# proyecto_diseno_2025_2.net
KiCad netlist of a schematic drawn in EasyEDA Pro
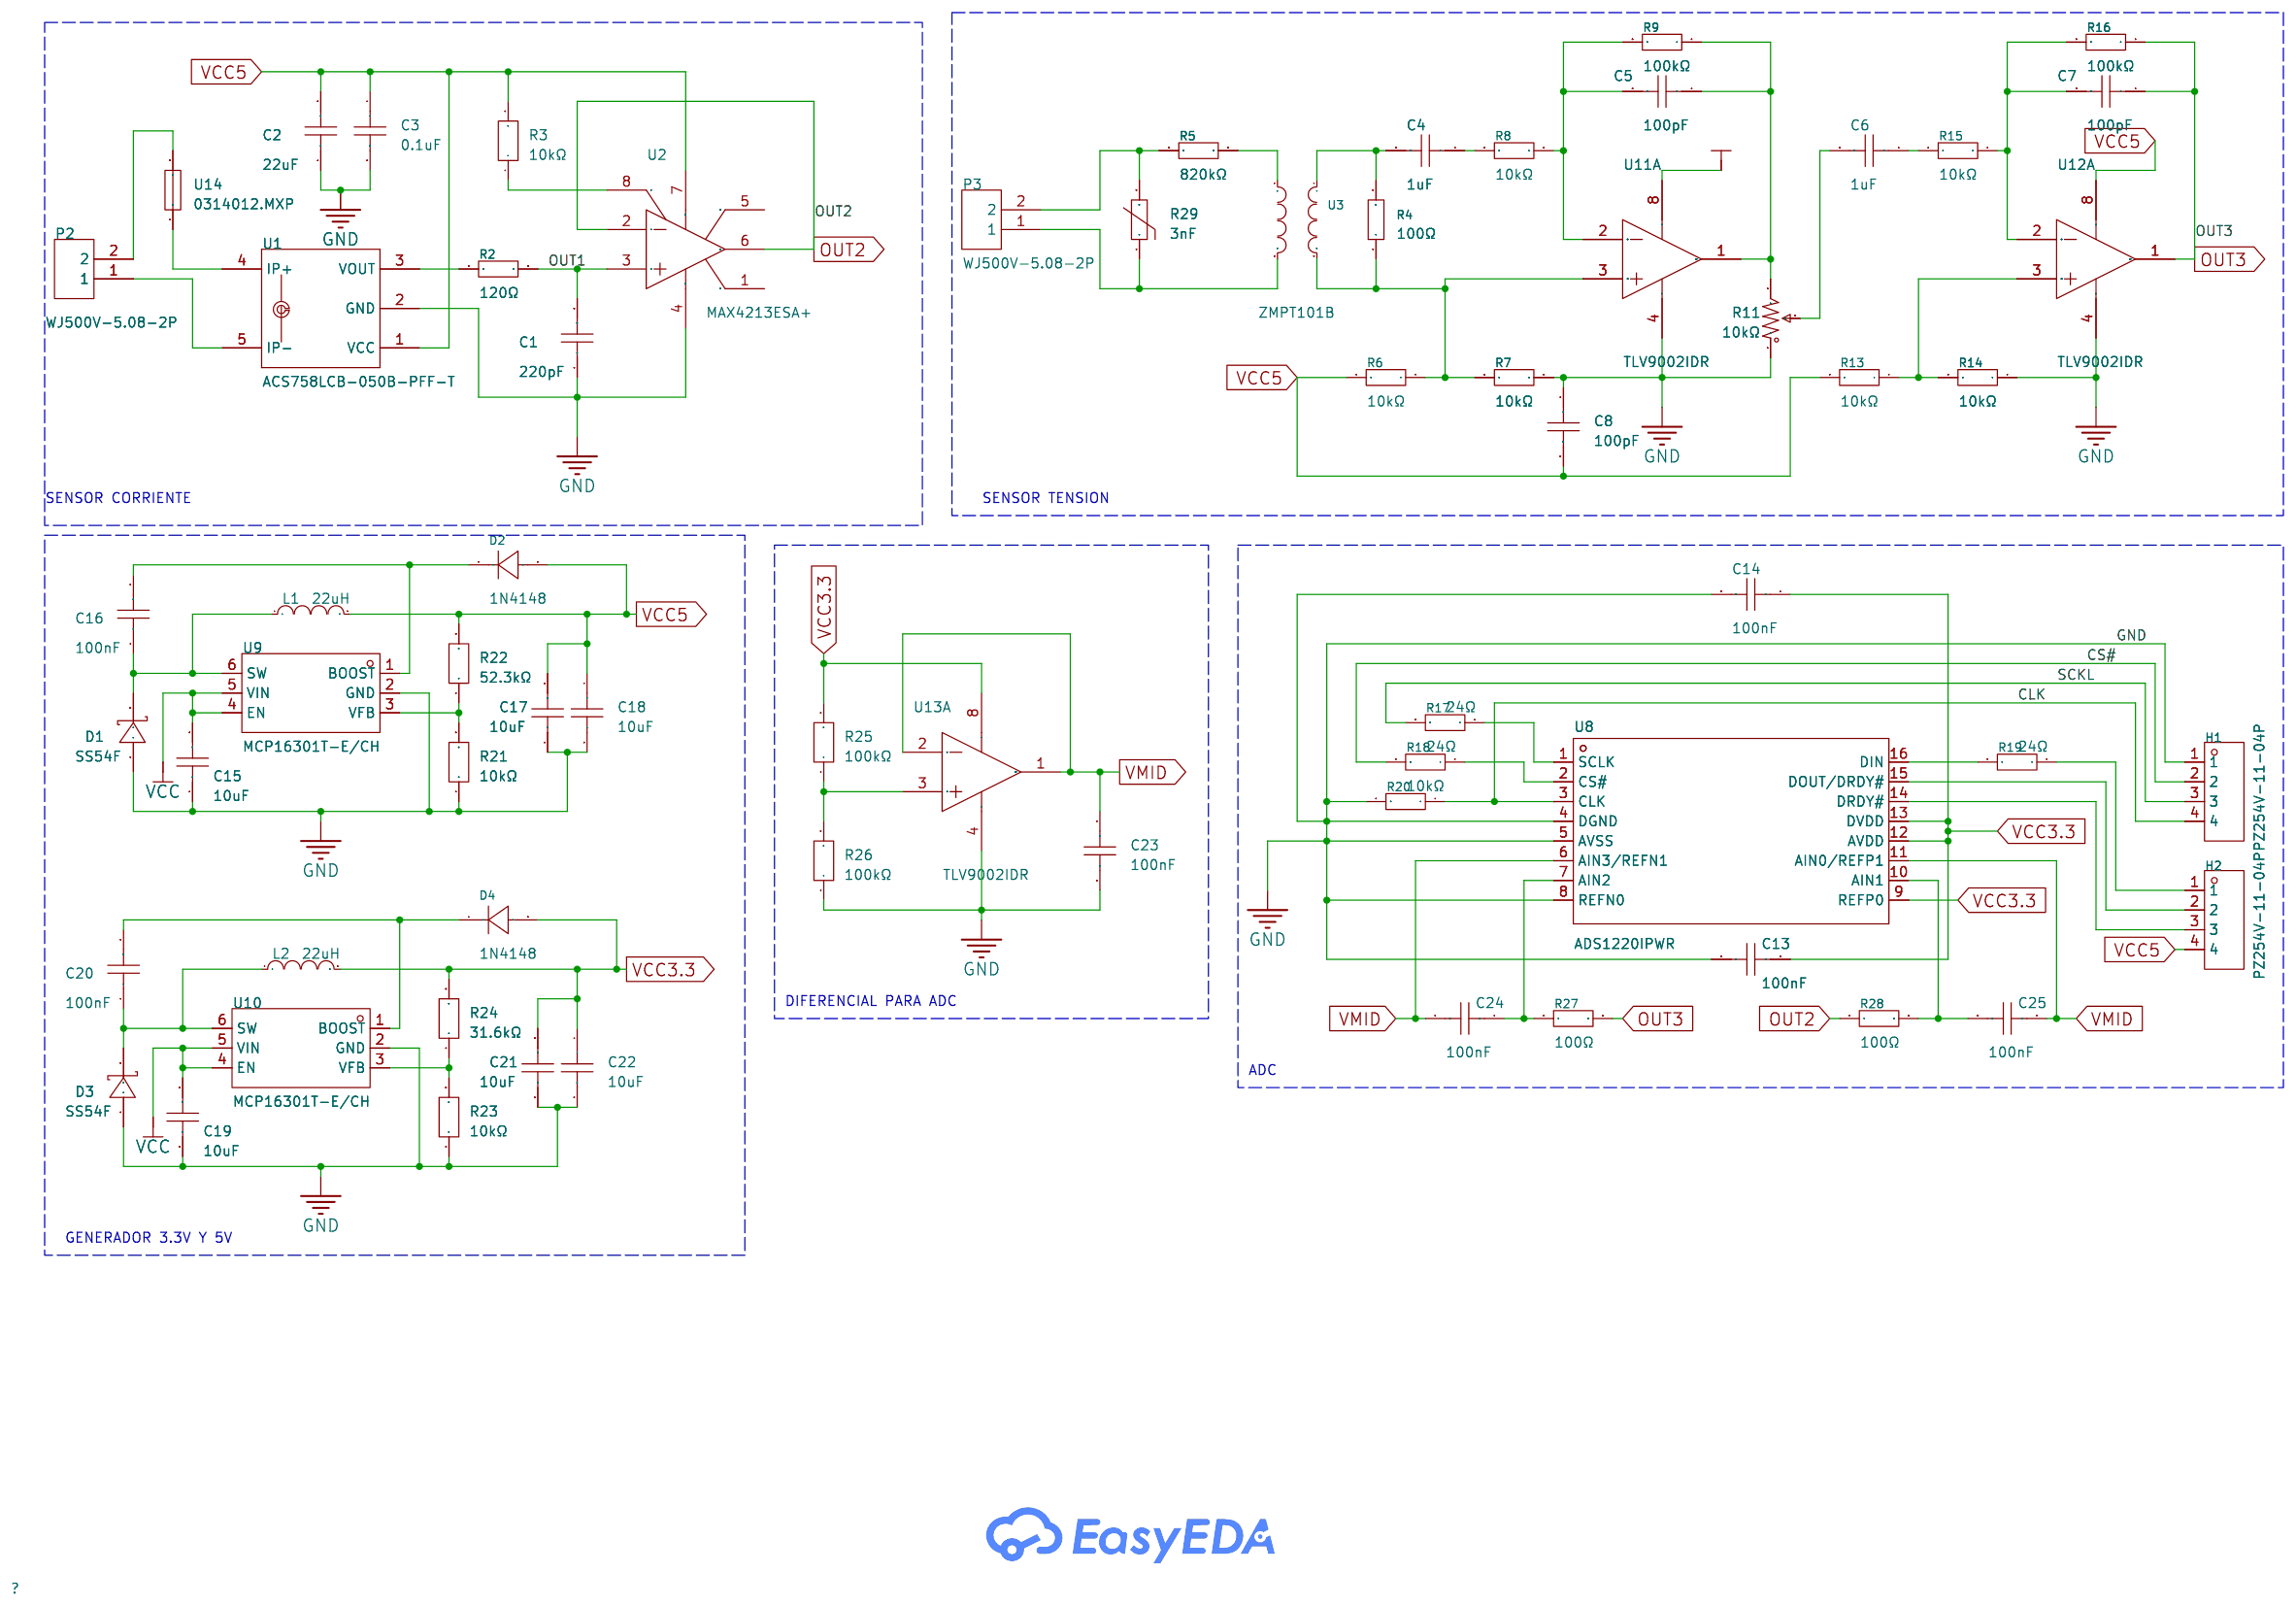
[diagram p0: schematic sheet]

(export (version "E")
  (design (tool "Eeschema 10.0.6"))
  (components
    (comp (ref "C1")
      (value "220pF")
      (footprint "easyedapro:C0603")
      (description "Capacitance:100nF Tolerance:±10% Tolerance:±10% Voltage Rating:50V Temperature Coefficient:X7R")
      (fields
        (field (name "Manufacturer Part") "CC0603KRX7R9BB104")
        (field (name "Manufacturer") "YAGEO(国巨)")
      )
      (libsource (lib "easyedapro") (part "CC0603KRX7R9BB104"))
    )
    (comp (ref "C2")
      (value "22uF")
      (footprint "easyedapro:C0603")
      (description "Capacitance:100nF Tolerance:±10% Tolerance:±10% Voltage Rating:50V Temperature Coefficient:X7R")
      (fields
        (field (name "Manufacturer Part") "CC0603KRX7R9BB104")
        (field (name "Manufacturer") "YAGEO(国巨)")
      )
      (libsource (lib "easyedapro") (part "CC0603KRX7R9BB104"))
    )
    (comp (ref "C3")
      (value "0.1uF")
      (footprint "easyedapro:C0603")
      (description "Capacitance:100nF Tolerance:±10% Tolerance:±10% Voltage Rating:50V Temperature Coefficient:X7R")
      (fields
        (field (name "Manufacturer Part") "CC0603KRX7R9BB104")
        (field (name "Manufacturer") "YAGEO(国巨)")
      )
      (libsource (lib "easyedapro") (part "CC0603KRX7R9BB104"))
    )
    (comp (ref "C4")
      (value "1uF")
      (footprint "easyedapro:C0603")
      (description "Capacitance:100nF Tolerance:±10% Tolerance:±10% Voltage Rating:50V Temperature Coefficient:X7R")
      (fields
        (field (name "Manufacturer Part") "CC0603KRX7R9BB104")
        (field (name "Manufacturer") "YAGEO(国巨)")
      )
      (libsource (lib "easyedapro") (part "CC0603KRX7R9BB104"))
    )
    (comp (ref "C5")
      (value "100pF")
      (footprint "easyedapro:C0603")
      (description "Capacitance:100nF Tolerance:±10% Tolerance:±10% Voltage Rating:50V Temperature Coefficient:X7R")
      (fields
        (field (name "Manufacturer Part") "CC0603KRX7R9BB104")
        (field (name "Manufacturer") "YAGEO(国巨)")
      )
      (libsource (lib "easyedapro") (part "CC0603KRX7R9BB104"))
    )
    (comp (ref "C6")
      (value "1uF")
      (footprint "easyedapro:C0603")
      (description "Capacitance:100nF Tolerance:±10% Tolerance:±10% Voltage Rating:50V Temperature Coefficient:X7R")
      (fields
        (field (name "Manufacturer Part") "CC0603KRX7R9BB104")
        (field (name "Manufacturer") "YAGEO(国巨)")
      )
      (libsource (lib "easyedapro") (part "CC0603KRX7R9BB104"))
    )
    (comp (ref "C7")
      (value "100pF")
      (footprint "easyedapro:C0603")
      (description "Capacitance:100nF Tolerance:±10% Tolerance:±10% Voltage Rating:50V Temperature Coefficient:X7R")
      (fields
        (field (name "Manufacturer Part") "CC0603KRX7R9BB104")
        (field (name "Manufacturer") "YAGEO(国巨)")
      )
      (libsource (lib "easyedapro") (part "CC0603KRX7R9BB104"))
    )
    (comp (ref "C8")
      (value "100pF")
      (footprint "easyedapro:C0603")
      (description "Capacitance:100nF Tolerance:±10% Tolerance:±10% Voltage Rating:50V Temperature Coefficient:X7R")
      (fields
        (field (name "Manufacturer Part") "CC0603KRX7R9BB104")
        (field (name "Manufacturer") "YAGEO(国巨)")
      )
      (libsource (lib "easyedapro") (part "CC0603KRX7R9BB104"))
    )
    (comp (ref "C13")
      (value "100nF")
      (footprint "easyedapro:C0603")
      (description "Capacitance:100nF Tolerance:±10% Tolerance:±10% Voltage Rating:50V Temperature Coefficient:X7R")
      (fields
        (field (name "Manufacturer Part") "CC0603KRX7R9BB104")
        (field (name "Manufacturer") "YAGEO(国巨)")
      )
      (libsource (lib "easyedapro") (part "CC0603KRX7R9BB104"))
    )
    (comp (ref "C14")
      (value "100nF")
      (footprint "easyedapro:C0603")
      (description "Capacitance:100nF Tolerance:±10% Tolerance:±10% Voltage Rating:50V Temperature Coefficient:X7R")
      (fields
        (field (name "Manufacturer Part") "CC0603KRX7R9BB104")
        (field (name "Manufacturer") "YAGEO(国巨)")
      )
      (libsource (lib "easyedapro") (part "CC0603KRX7R9BB104"))
    )
    (comp (ref "C15")
      (value "10uF")
      (footprint "easyedapro:C0603")
      (description "Capacitance:100nF Tolerance:±10% Tolerance:±10% Voltage Rating:50V Temperature Coefficient:X7R")
      (fields
        (field (name "Manufacturer Part") "CC0603KRX7R9BB104")
        (field (name "Manufacturer") "YAGEO(国巨)")
      )
      (libsource (lib "easyedapro") (part "CC0603KRX7R9BB104"))
    )
    (comp (ref "C16")
      (value "100nF")
      (footprint "easyedapro:C0603")
      (description "Capacitance:100nF Tolerance:±10% Tolerance:±10% Voltage Rating:50V Temperature Coefficient:X7R")
      (fields
        (field (name "Manufacturer Part") "CC0603KRX7R9BB104")
        (field (name "Manufacturer") "YAGEO(国巨)")
      )
      (libsource (lib "easyedapro") (part "CC0603KRX7R9BB104"))
    )
    (comp (ref "C17")
      (value "10uF")
      (footprint "easyedapro:C0603")
      (description "Capacitance:100nF Tolerance:±10% Tolerance:±10% Voltage Rating:50V Temperature Coefficient:X7R")
      (fields
        (field (name "Manufacturer Part") "CC0603KRX7R9BB104")
        (field (name "Manufacturer") "YAGEO(国巨)")
      )
      (libsource (lib "easyedapro") (part "CC0603KRX7R9BB104"))
    )
    (comp (ref "C18")
      (value "10uF")
      (footprint "easyedapro:C0603")
      (description "Capacitance:100nF Tolerance:±10% Tolerance:±10% Voltage Rating:50V Temperature Coefficient:X7R")
      (fields
        (field (name "Manufacturer Part") "CC0603KRX7R9BB104")
        (field (name "Manufacturer") "YAGEO(国巨)")
      )
      (libsource (lib "easyedapro") (part "CC0603KRX7R9BB104"))
    )
    (comp (ref "C19")
      (value "10uF")
      (footprint "easyedapro:C0603")
      (description "Capacitance:100nF Tolerance:±10% Tolerance:±10% Voltage Rating:50V Temperature Coefficient:X7R")
      (fields
        (field (name "Manufacturer Part") "CC0603KRX7R9BB104")
        (field (name "Manufacturer") "YAGEO(国巨)")
      )
      (libsource (lib "easyedapro") (part "CC0603KRX7R9BB104"))
    )
    (comp (ref "C20")
      (value "100nF")
      (footprint "easyedapro:C0603")
      (description "Capacitance:100nF Tolerance:±10% Tolerance:±10% Voltage Rating:50V Temperature Coefficient:X7R")
      (fields
        (field (name "Manufacturer Part") "CC0603KRX7R9BB104")
        (field (name "Manufacturer") "YAGEO(国巨)")
      )
      (libsource (lib "easyedapro") (part "CC0603KRX7R9BB104"))
    )
    (comp (ref "C21")
      (value "10uF")
      (footprint "easyedapro:C0603")
      (description "Capacitance:100nF Tolerance:±10% Tolerance:±10% Voltage Rating:50V Temperature Coefficient:X7R")
      (fields
        (field (name "Manufacturer Part") "CC0603KRX7R9BB104")
        (field (name "Manufacturer") "YAGEO(国巨)")
      )
      (libsource (lib "easyedapro") (part "CC0603KRX7R9BB104"))
    )
    (comp (ref "C22")
      (value "10uF")
      (footprint "easyedapro:C0603")
      (description "Capacitance:100nF Tolerance:±10% Tolerance:±10% Voltage Rating:50V Temperature Coefficient:X7R")
      (fields
        (field (name "Manufacturer Part") "CC0603KRX7R9BB104")
        (field (name "Manufacturer") "YAGEO(国巨)")
      )
      (libsource (lib "easyedapro") (part "CC0603KRX7R9BB104"))
    )
    (comp (ref "C23")
      (value "100nF")
      (footprint "easyedapro:C0603")
      (description "Capacitance:100nF Tolerance:±10% Tolerance:±10% Voltage Rating:50V Temperature Coefficient:X7R")
      (fields
        (field (name "Manufacturer Part") "CC0603KRX7R9BB104")
        (field (name "Manufacturer") "YAGEO(国巨)")
      )
      (libsource (lib "easyedapro") (part "CC0603KRX7R9BB104"))
    )
    (comp (ref "C24")
      (value "100nF")
      (footprint "easyedapro:C0603")
      (description "Capacitance:100nF Tolerance:±10% Tolerance:±10% Voltage Rating:50V Temperature Coefficient:X7R")
      (fields
        (field (name "Manufacturer Part") "CC0603KRX7R9BB104")
        (field (name "Manufacturer") "YAGEO(国巨)")
      )
      (libsource (lib "easyedapro") (part "CC0603KRX7R9BB104"))
    )
    (comp (ref "C25")
      (value "100nF")
      (footprint "easyedapro:C0603")
      (description "Capacitance:100nF Tolerance:±10% Tolerance:±10% Voltage Rating:50V Temperature Coefficient:X7R")
      (fields
        (field (name "Manufacturer Part") "CC0603KRX7R9BB104")
        (field (name "Manufacturer") "YAGEO(国巨)")
      )
      (libsource (lib "easyedapro") (part "CC0603KRX7R9BB104"))
    )
    (comp (ref "D1")
      (value "SS54F")
      (footprint "easyedapro:SMAF_L3.5-W2.6-LS4.7-FD")
      (fields (field (name "Manufacturer") "High Diode(海德)"))
      (libsource (lib "easyedapro") (part "SS54F_C524830"))
    )
    (comp (ref "D2")
      (value "1N4148")
      (footprint "easyedapro:DO-35_BD2.0-L4.2-P8.20-D0.5-RD")
      (fields (field (name "Manufacturer") "SMC(桑德斯)"))
      (libsource (lib "easyedapro") (part "1N4148_C493188"))
    )
    (comp (ref "D3")
      (value "SS54F")
      (footprint "easyedapro:SMAF_L3.5-W2.6-LS4.7-FD")
      (fields (field (name "Manufacturer") "High Diode(海德)"))
      (libsource (lib "easyedapro") (part "SS54F_C524830"))
    )
    (comp (ref "D4")
      (value "1N4148")
      (footprint "easyedapro:DO-35_BD2.0-L4.2-P8.20-D0.5-RD")
      (fields (field (name "Manufacturer") "SMC(桑德斯)"))
      (libsource (lib "easyedapro") (part "1N4148_C493188"))
    )
    (comp (ref "H1")
      (value "PZ254V-11-04P")
      (footprint "easyedapro:HDR-TH_4P-P2.54-V-M")
      (fields (field (name "Manufacturer") "XFCN(兴飞)"))
      (libsource (lib "easyedapro") (part "PZ254V-11-04P_C2691448"))
    )
    (comp (ref "H2")
      (value "PZ254V-11-04P")
      (footprint "easyedapro:HDR-TH_4P-P2.54-V-M")
      (fields (field (name "Manufacturer") "XFCN(兴飞)"))
      (libsource (lib "easyedapro") (part "PZ254V-11-04P_C2691448"))
    )
    (comp (ref "L1") (value "22uH") (footprint "easyedapro:L0603") (libsource (lib "easyedapro") (part "电感")))
    (comp (ref "L2") (value "22uH") (footprint "easyedapro:L0603") (libsource (lib "easyedapro") (part "电感")))
    (comp (ref "P2")
      (value "WJ500V-5.08-2P")
      (footprint "easyedapro:CONN-TH_2P-P5.00_WJ500V-5.08-2P")
      (fields (field (name "Manufacturer") "KANGNEX(康奈克斯电气)"))
      (libsource (lib "easyedapro") (part "WJ500V-5.08-2P-14-00A"))
    )
    (comp (ref "P3")
      (value "WJ500V-5.08-2P")
      (footprint "easyedapro:CONN-TH_2P-P5.00_WJ500V-5.08-2P")
      (fields (field (name "Manufacturer") "KANGNEX(康奈克斯电气)"))
      (libsource (lib "easyedapro") (part "WJ500V-5.08-2P-14-00A"))
    )
    (comp (ref "R2")
      (value "120Ω")
      (footprint "easyedapro:R0603")
      (fields
        (field (name "Manufacturer Part") "0603WAF1200T5E")
        (field (name "Manufacturer") "UNI-ROYAL(厚声)")
      )
      (libsource (lib "easyedapro") (part "0603WAF1200T5E"))
    )
    (comp (ref "R3")
      (value "10kΩ")
      (footprint "easyedapro:R0603")
      (fields (field (name "Manufacturer Part") "FRC0603J103 TS") (field (name "Manufacturer") "FOJAN(富捷)"))
      (libsource (lib "easyedapro") (part "FRC0603J103TS"))
    )
    (comp (ref "R4")
      (value "100Ω")
      (footprint "easyedapro:R0603")
      (fields
        (field (name "Manufacturer Part") "0603WAF1200T5E")
        (field (name "Manufacturer") "UNI-ROYAL(厚声)")
      )
      (libsource (lib "easyedapro") (part "0603WAF1200T5E"))
    )
    (comp (ref "R5")
      (value "820kΩ")
      (footprint "easyedapro:R0603")
      (fields
        (field (name "Manufacturer Part") "0603WAF1200T5E")
        (field (name "Manufacturer") "UNI-ROYAL(厚声)")
      )
      (libsource (lib "easyedapro") (part "0603WAF1200T5E"))
    )
    (comp (ref "R6")
      (value "10kΩ")
      (footprint "easyedapro:R0603")
      (fields
        (field (name "Manufacturer Part") "0603WAF1200T5E")
        (field (name "Manufacturer") "UNI-ROYAL(厚声)")
      )
      (libsource (lib "easyedapro") (part "0603WAF1200T5E"))
    )
    (comp (ref "R7")
      (value "10kΩ")
      (footprint "easyedapro:R0603")
      (fields
        (field (name "Manufacturer Part") "0603WAF1200T5E")
        (field (name "Manufacturer") "UNI-ROYAL(厚声)")
      )
      (libsource (lib "easyedapro") (part "0603WAF1200T5E"))
    )
    (comp (ref "R8")
      (value "10kΩ")
      (footprint "easyedapro:R0603")
      (fields
        (field (name "Manufacturer Part") "0603WAF1200T5E")
        (field (name "Manufacturer") "UNI-ROYAL(厚声)")
      )
      (libsource (lib "easyedapro") (part "0603WAF1200T5E"))
    )
    (comp (ref "R9")
      (value "100kΩ")
      (footprint "easyedapro:R0603")
      (fields
        (field (name "Manufacturer Part") "0603WAF1200T5E")
        (field (name "Manufacturer") "UNI-ROYAL(厚声)")
      )
      (libsource (lib "easyedapro") (part "0603WAF1200T5E"))
    )
    (comp (ref "R11")
      (value "10kΩ")
      (footprint "easyedapro:RES-ADJ-TH_3P-L10.0-W10.0-P2.50-L")
      (fields (field (name "Manufacturer Part") "3296W-1-103") (field (name "Manufacturer") "BOCHEN(博晨)"))
      (libsource (lib "easyedapro") (part "3296W-1-103"))
    )
    (comp (ref "R13")
      (value "10kΩ")
      (footprint "easyedapro:R0603")
      (fields
        (field (name "Manufacturer Part") "0603WAF1200T5E")
        (field (name "Manufacturer") "UNI-ROYAL(厚声)")
      )
      (libsource (lib "easyedapro") (part "0603WAF1200T5E"))
    )
    (comp (ref "R14")
      (value "10kΩ")
      (footprint "easyedapro:R0603")
      (fields
        (field (name "Manufacturer Part") "0603WAF1200T5E")
        (field (name "Manufacturer") "UNI-ROYAL(厚声)")
      )
      (libsource (lib "easyedapro") (part "0603WAF1200T5E"))
    )
    (comp (ref "R15")
      (value "10kΩ")
      (footprint "easyedapro:R0603")
      (fields
        (field (name "Manufacturer Part") "0603WAF1200T5E")
        (field (name "Manufacturer") "UNI-ROYAL(厚声)")
      )
      (libsource (lib "easyedapro") (part "0603WAF1200T5E"))
    )
    (comp (ref "R16")
      (value "100kΩ")
      (footprint "easyedapro:R0603")
      (fields
        (field (name "Manufacturer Part") "0603WAF1200T5E")
        (field (name "Manufacturer") "UNI-ROYAL(厚声)")
      )
      (libsource (lib "easyedapro") (part "0603WAF1200T5E"))
    )
    (comp (ref "R17")
      (value "24Ω")
      (footprint "easyedapro:R0603")
      (fields
        (field (name "Manufacturer Part") "0603WAF1200T5E")
        (field (name "Manufacturer") "UNI-ROYAL(厚声)")
      )
      (libsource (lib "easyedapro") (part "0603WAF1200T5E"))
    )
    (comp (ref "R18")
      (value "24Ω")
      (footprint "easyedapro:R0603")
      (fields
        (field (name "Manufacturer Part") "0603WAF1200T5E")
        (field (name "Manufacturer") "UNI-ROYAL(厚声)")
      )
      (libsource (lib "easyedapro") (part "0603WAF1200T5E"))
    )
    (comp (ref "R19")
      (value "24Ω")
      (footprint "easyedapro:R0603")
      (fields
        (field (name "Manufacturer Part") "0603WAF1200T5E")
        (field (name "Manufacturer") "UNI-ROYAL(厚声)")
      )
      (libsource (lib "easyedapro") (part "0603WAF1200T5E"))
    )
    (comp (ref "R20")
      (value "10kΩ")
      (footprint "easyedapro:R0603")
      (fields
        (field (name "Manufacturer Part") "0603WAF1200T5E")
        (field (name "Manufacturer") "UNI-ROYAL(厚声)")
      )
      (libsource (lib "easyedapro") (part "0603WAF1200T5E"))
    )
    (comp (ref "R21")
      (value "10kΩ")
      (footprint "easyedapro:R0603")
      (fields (field (name "Manufacturer Part") "FRC0603J103 TS") (field (name "Manufacturer") "FOJAN(富捷)"))
      (libsource (lib "easyedapro") (part "FRC0603J103TS"))
    )
    (comp (ref "R22")
      (value "52.3kΩ")
      (footprint "easyedapro:R0603")
      (fields (field (name "Manufacturer Part") "FRC0603J103 TS") (field (name "Manufacturer") "FOJAN(富捷)"))
      (libsource (lib "easyedapro") (part "FRC0603J103TS"))
    )
    (comp (ref "R23")
      (value "10kΩ")
      (footprint "easyedapro:R0603")
      (fields (field (name "Manufacturer Part") "FRC0603J103 TS") (field (name "Manufacturer") "FOJAN(富捷)"))
      (libsource (lib "easyedapro") (part "FRC0603J103TS"))
    )
    (comp (ref "R24")
      (value "31.6kΩ")
      (footprint "easyedapro:R0603")
      (fields (field (name "Manufacturer Part") "FRC0603J103 TS") (field (name "Manufacturer") "FOJAN(富捷)"))
      (libsource (lib "easyedapro") (part "FRC0603J103TS"))
    )
    (comp (ref "R25")
      (value "100kΩ")
      (footprint "easyedapro:R0603")
      (fields (field (name "Manufacturer Part") "FRC0603J103 TS") (field (name "Manufacturer") "FOJAN(富捷)"))
      (libsource (lib "easyedapro") (part "FRC0603J103TS"))
    )
    (comp (ref "R26")
      (value "100kΩ")
      (footprint "easyedapro:R0603")
      (fields (field (name "Manufacturer Part") "FRC0603J103 TS") (field (name "Manufacturer") "FOJAN(富捷)"))
      (libsource (lib "easyedapro") (part "FRC0603J103TS"))
    )
    (comp (ref "R27")
      (value "100Ω")
      (footprint "easyedapro:R0603")
      (fields
        (field (name "Manufacturer Part") "0603WAF1200T5E")
        (field (name "Manufacturer") "UNI-ROYAL(厚声)")
      )
      (libsource (lib "easyedapro") (part "0603WAF1200T5E"))
    )
    (comp (ref "R28")
      (value "100Ω")
      (footprint "easyedapro:R0603")
      (fields
        (field (name "Manufacturer Part") "0603WAF1200T5E")
        (field (name "Manufacturer") "UNI-ROYAL(厚声)")
      )
      (libsource (lib "easyedapro") (part "0603WAF1200T5E"))
    )
    (comp (ref "R29")
      (value "3nF")
      (footprint "easyedapro:RES-TH_L15.5-W4.6-P7.50-D0.8-S3.00")
      (fields (field (name "Manufacturer Part") "14D151K") (field (name "Manufacturer") "R+O(宏嘉诚)"))
      (libsource (lib "easyedapro") (part "14D151K"))
    )
    (comp (ref "U1")
      (value "ACS758LCB-050B-PFF-T")
      (footprint "easyedapro:SENSOR-TH_ACS758LCB-050B-PFF-T")
      (fields (field (name "Manufacturer") "JSMSEMI(杰盛微)"))
      (libsource (lib "easyedapro") (part "ACS758LCB-050B-PFF-T_C6396157"))
    )
    (comp (ref "U2")
      (value "MAX4213ESA+")
      (footprint "easyedapro:SO-8_L4.9-W3.9-P1.27-LS5.9-BL")
      (fields (field (name "Manufacturer") "ADI(亚德诺)/MAXIM(美信)"))
      (libsource (lib "easyedapro") (part "MAX4213ESA+"))
    )
    (comp (ref "U3")
      (value "ZMPT101B")
      (footprint "easyedapro:XFMR-TH_ZMPT101B")
      (fields (field (name "Manufacturer") "择明朗熙"))
      (libsource (lib "easyedapro") (part "ZMPT101B"))
    )
    (comp (ref "U8")
      (value "ADS1220IPWR")
      (footprint "easyedapro:TSSOP-16_L5.0-W4.4-P0.65-LS6.4-BL")
      (fields (field (name "Manufacturer") "TI(德州仪器)"))
      (libsource (lib "easyedapro") (part "ADS1220IPWR"))
    )
    (comp (ref "U9")
      (value "MCP16301T-E/CH")
      (footprint "easyedapro:SOT-23-6_L2.9-W1.6-P0.95-LS2.8-BR")
      (fields (field (name "Manufacturer") "MICROCHIP(美国微芯)"))
      (libsource (lib "easyedapro") (part "MCP16301T-E/CH"))
    )
    (comp (ref "U10")
      (value "MCP16301T-E/CH")
      (footprint "easyedapro:SOT-23-6_L2.9-W1.6-P0.95-LS2.8-BR")
      (fields (field (name "Manufacturer") "MICROCHIP(美国微芯)"))
      (libsource (lib "easyedapro") (part "MCP16301T-E/CH"))
    )
    (comp (ref "U11")
      (value "TLV9002IDR")
      (footprint "easyedapro:SOIC-8_L4.9-W3.9-P1.27-LS6.0-BL")
      (fields (field (name "Manufacturer") "TI(德州仪器)"))
      (libsource (lib "easyedapro") (part "TLV9002IDR"))
    )
    (comp (ref "U12")
      (value "TLV9002IDR")
      (footprint "easyedapro:SOIC-8_L4.9-W3.9-P1.27-LS6.0-BL")
      (fields (field (name "Manufacturer") "TI(德州仪器)"))
      (libsource (lib "easyedapro") (part "TLV9002IDR"))
    )
    (comp (ref "U13")
      (value "TLV9002IDR")
      (footprint "easyedapro:SOIC-8_L4.9-W3.9-P1.27-LS6.0-BL")
      (fields (field (name "Manufacturer") "TI(德州仪器)"))
      (libsource (lib "easyedapro") (part "TLV9002IDR"))
    )
    (comp (ref "U14")
      (value "0314012.MXP")
      (footprint "easyedapro:FUSE-SMD_BD6.4-L31.8_0314020.MXP")
      (description "Type:Ceramic Tube Fuse Current Rating:12A")
      (fields (field (name "Manufacturer") "Littelfuse(美国力特)"))
      (libsource (lib "easyedapro") (part "0314012.MXP"))
    )
  )
  (nets
    (net (code "1") (name "/CLK") (class "Default")
      (node (ref "H1") (pin "4") (pinfunction "4_4") (pintype "input"))
      (node (ref "R20") (pin "1") (pinfunction "1_1") (pintype "input"))
      (node (ref "U8") (pin "3") (pinfunction "CLK_3") (pintype "unspecified"))
    )
    (net (code "2") (name "/CS#") (class "Default")
      (node (ref "H1") (pin "2") (pinfunction "2_2") (pintype "input"))
      (node (ref "R18") (pin "2") (pinfunction "2_2") (pintype "input"))
    )
    (net (code "3") (name "/OUT1") (class "Default")
      (node (ref "C1") (pin "2") (pinfunction "2_2") (pintype "unspecified"))
      (node (ref "R2") (pin "2") (pinfunction "2_2") (pintype "input"))
      (node (ref "U2") (pin "3") (pinfunction "IN+_3") (pintype "unspecified"))
    )
    (net (code "4") (name "/SCKL") (class "Default")
      (node (ref "H1") (pin "3") (pinfunction "3_3") (pintype "input"))
      (node (ref "R17") (pin "2") (pinfunction "2_2") (pintype "input"))
    )
    (net (code "5") (name "GND") (class "Default")
      (node (ref "C1") (pin "1") (pinfunction "1_1") (pintype "unspecified"))
      (node (ref "C13") (pin "2") (pinfunction "2_2") (pintype "unspecified"))
      (node (ref "C14") (pin "2") (pinfunction "2_2") (pintype "unspecified"))
      (node (ref "C15") (pin "1") (pinfunction "1_1") (pintype "unspecified"))
      (node (ref "C17") (pin "1") (pinfunction "1_1") (pintype "unspecified"))
      (node (ref "C18") (pin "2") (pinfunction "2_2") (pintype "unspecified"))
      (node (ref "C19") (pin "1") (pinfunction "1_1") (pintype "unspecified"))
      (node (ref "C2") (pin "1") (pinfunction "1_1") (pintype "unspecified"))
      (node (ref "C21") (pin "1") (pinfunction "1_1") (pintype "unspecified"))
      (node (ref "C22") (pin "2") (pinfunction "2_2") (pintype "unspecified"))
      (node (ref "C23") (pin "2") (pinfunction "2_2") (pintype "unspecified"))
      (node (ref "C3") (pin "2") (pinfunction "2_2") (pintype "unspecified"))
      (node (ref "C8") (pin "1") (pinfunction "1_1") (pintype "unspecified"))
      (node (ref "D1") (pin "1") (pinfunction "A_1") (pintype "unspecified"))
      (node (ref "D3") (pin "1") (pinfunction "A_1") (pintype "unspecified"))
      (node (ref "H1") (pin "1") (pinfunction "1_1") (pintype "input"))
      (node (ref "R11") (pin "1") (pinfunction "1_1") (pintype "input"))
      (node (ref "R14") (pin "1") (pinfunction "1_1") (pintype "input"))
      (node (ref "R20") (pin "2") (pinfunction "2_2") (pintype "input"))
      (node (ref "R21") (pin "1") (pinfunction "1_1") (pintype "unspecified"))
      (node (ref "R23") (pin "1") (pinfunction "1_1") (pintype "unspecified"))
      (node (ref "R26") (pin "1") (pinfunction "1_1") (pintype "unspecified"))
      (node (ref "R7") (pin "1") (pinfunction "1_1") (pintype "input"))
      (node (ref "U1") (pin "2") (pinfunction "GND_2") (pintype "unspecified"))
      (node (ref "U10") (pin "2") (pinfunction "GND_2") (pintype "unspecified"))
      (node (ref "U11") (pin "4") (pinfunction "V-_4") (pintype "unspecified"))
      (node (ref "U12") (pin "4") (pinfunction "V-_4") (pintype "unspecified"))
      (node (ref "U13") (pin "4") (pinfunction "V-_4") (pintype "unspecified"))
      (node (ref "U2") (pin "4") (pinfunction "VEE_4") (pintype "unspecified"))
      (node (ref "U8") (pin "4") (pinfunction "DGND_4") (pintype "unspecified"))
      (node (ref "U8") (pin "5") (pinfunction "AVSS_5") (pintype "unspecified"))
      (node (ref "U8") (pin "8") (pinfunction "REFN0_8") (pintype "unspecified"))
      (node (ref "U9") (pin "2") (pinfunction "GND_2") (pintype "unspecified"))
    )
    (net (code "6") (name "Net-(C4-Pad1)") (class "Default")
      (node (ref "C4") (pin "1") (pinfunction "1_1") (pintype "unspecified"))
      (node (ref "R8") (pin "2") (pinfunction "2_2") (pintype "input"))
    )
    (net (code "7") (name "Net-(C4-Pad2)") (class "Default")
      (node (ref "C4") (pin "2") (pinfunction "2_2") (pintype "unspecified"))
      (node (ref "R4") (pin "2") (pinfunction "2_2") (pintype "input"))
      (node (ref "U3") (pin "4") (pinfunction "4_4") (pintype "input"))
    )
    (net (code "8") (name "Net-(C6-Pad1)") (class "Default")
      (node (ref "C6") (pin "1") (pinfunction "1_1") (pintype "unspecified"))
      (node (ref "R15") (pin "2") (pinfunction "2_2") (pintype "input"))
    )
    (net (code "9") (name "Net-(C6-Pad2)") (class "Default")
      (node (ref "C6") (pin "2") (pinfunction "2_2") (pintype "unspecified"))
      (node (ref "R11") (pin "2") (pinfunction "2_2") (pintype "input"))
    )
    (net (code "10") (name "Net-(D1-K)") (class "Default")
      (node (ref "C16") (pin "1") (pinfunction "1_1") (pintype "unspecified"))
      (node (ref "D1") (pin "2") (pinfunction "K_2") (pintype "unspecified"))
      (node (ref "L1") (pin "1") (pinfunction "1_1") (pintype "input"))
      (node (ref "U9") (pin "6") (pinfunction "SW_6") (pintype "unspecified"))
    )
    (net (code "11") (name "Net-(D2-K)") (class "Default")
      (node (ref "C16") (pin "2") (pinfunction "2_2") (pintype "unspecified"))
      (node (ref "D2") (pin "1") (pinfunction "K_1") (pintype "input"))
      (node (ref "U9") (pin "1") (pinfunction "BOOST_1") (pintype "unspecified"))
    )
    (net (code "12") (name "Net-(D3-K)") (class "Default")
      (node (ref "C20") (pin "1") (pinfunction "1_1") (pintype "unspecified"))
      (node (ref "D3") (pin "2") (pinfunction "K_2") (pintype "unspecified"))
      (node (ref "L2") (pin "1") (pinfunction "1_1") (pintype "input"))
      (node (ref "U10") (pin "6") (pinfunction "SW_6") (pintype "unspecified"))
    )
    (net (code "13") (name "Net-(D4-K)") (class "Default")
      (node (ref "C20") (pin "2") (pinfunction "2_2") (pintype "unspecified"))
      (node (ref "D4") (pin "1") (pinfunction "K_1") (pintype "input"))
      (node (ref "U10") (pin "1") (pinfunction "BOOST_1") (pintype "unspecified"))
    )
    (net (code "14") (name "Net-(H2-Pad1)") (class "Default")
      (node (ref "H2") (pin "1") (pinfunction "1_1") (pintype "input"))
      (node (ref "R19") (pin "1") (pinfunction "1_1") (pintype "input"))
    )
    (net (code "15") (name "Net-(P2-Pad2)") (class "Default")
      (node (ref "P2") (pin "2") (pinfunction "2_2") (pintype "unspecified"))
      (node (ref "U14") (pin "2") (pinfunction "2_2") (pintype "unspecified"))
    )
    (net (code "16") (name "Net-(P3-Pad1)") (class "Default")
      (node (ref "P3") (pin "1") (pinfunction "1_1") (pintype "unspecified"))
      (node (ref "R29") (pin "1") (pinfunction "1_1") (pintype "unspecified"))
      (node (ref "U3") (pin "2") (pinfunction "2_2") (pintype "input"))
    )
    (net (code "17") (name "Net-(P3-Pad2)") (class "Default")
      (node (ref "P3") (pin "2") (pinfunction "2_2") (pintype "unspecified"))
      (node (ref "R29") (pin "2") (pinfunction "2_2") (pintype "unspecified"))
      (node (ref "R5") (pin "2") (pinfunction "2_2") (pintype "input"))
    )
    (net (code "18") (name "Net-(R5-Pad1)") (class "Default")
      (node (ref "R5") (pin "1") (pinfunction "1_1") (pintype "input"))
      (node (ref "U3") (pin "1") (pinfunction "1_1") (pintype "input"))
    )
    (net (code "19") (name "Net-(U1-IP+)") (class "Default")
      (node (ref "U1") (pin "4") (pinfunction "IP+_4") (pintype "unspecified"))
      (node (ref "U14") (pin "1") (pinfunction "1_1") (pintype "unspecified"))
    )
    (net (code "20") (name "Net-(U1-IP-)") (class "Default")
      (node (ref "P2") (pin "1") (pinfunction "1_1") (pintype "unspecified"))
      (node (ref "U1") (pin "5") (pinfunction "IP-_5") (pintype "unspecified"))
    )
    (net (code "21") (name "Net-(U1-VOUT)") (class "Default")
      (node (ref "R2") (pin "1") (pinfunction "1_1") (pintype "input"))
      (node (ref "U1") (pin "3") (pinfunction "VOUT_3") (pintype "output"))
    )
    (net (code "22") (name "Net-(U2-EN)") (class "Default")
      (node (ref "R3") (pin "1") (pinfunction "1_1") (pintype "unspecified"))
      (node (ref "U2") (pin "8") (pinfunction "EN_8") (pintype "unspecified"))
    )
    (net (code "23") (name "Net-(U8-AIN1)") (class "Default")
      (node (ref "C25") (pin "2") (pinfunction "2_2") (pintype "unspecified"))
      (node (ref "R28") (pin "2") (pinfunction "2_2") (pintype "input"))
      (node (ref "U8") (pin "10") (pinfunction "AIN1_10") (pintype "unspecified"))
    )
    (net (code "24") (name "Net-(U8-AIN2)") (class "Default")
      (node (ref "C24") (pin "1") (pinfunction "1_1") (pintype "unspecified"))
      (node (ref "R27") (pin "1") (pinfunction "1_1") (pintype "input"))
      (node (ref "U8") (pin "7") (pinfunction "AIN2_7") (pintype "unspecified"))
    )
    (net (code "25") (name "Net-(U8-CS#)") (class "Default")
      (node (ref "R18") (pin "1") (pinfunction "1_1") (pintype "input"))
      (node (ref "U8") (pin "2") (pinfunction "CS#_2") (pintype "unspecified"))
    )
    (net (code "26") (name "Net-(U8-DIN)") (class "Default")
      (node (ref "R19") (pin "2") (pinfunction "2_2") (pintype "input"))
      (node (ref "U8") (pin "16") (pinfunction "DIN_16") (pintype "unspecified"))
    )
    (net (code "27") (name "Net-(U8-DOUT{slash}DRDY#)") (class "Default")
      (node (ref "H2") (pin "2") (pinfunction "2_2") (pintype "input"))
      (node (ref "U8") (pin "15") (pinfunction "DOUT/DRDY#_15") (pintype "unspecified"))
    )
    (net (code "28") (name "Net-(U8-DRDY#)") (class "Default")
      (node (ref "H2") (pin "3") (pinfunction "3_3") (pintype "input"))
      (node (ref "U8") (pin "14") (pinfunction "DRDY#_14") (pintype "unspecified"))
    )
    (net (code "29") (name "Net-(U8-SCLK)") (class "Default")
      (node (ref "R17") (pin "1") (pinfunction "1_1") (pintype "input"))
      (node (ref "U8") (pin "1") (pinfunction "SCLK_1") (pintype "unspecified"))
    )
    (net (code "30") (name "Net-(U9-VFB)") (class "Default")
      (node (ref "R21") (pin "2") (pinfunction "2_2") (pintype "unspecified"))
      (node (ref "R22") (pin "1") (pinfunction "1_1") (pintype "unspecified"))
      (node (ref "U9") (pin "3") (pinfunction "VFB_3") (pintype "unspecified"))
    )
    (net (code "31") (name "Net-(U10-VFB)") (class "Default")
      (node (ref "R23") (pin "2") (pinfunction "2_2") (pintype "unspecified"))
      (node (ref "R24") (pin "1") (pinfunction "1_1") (pintype "unspecified"))
      (node (ref "U10") (pin "3") (pinfunction "VFB_3") (pintype "unspecified"))
    )
    (net (code "32") (name "Net-(U11A-IN1+)") (class "Default")
      (node (ref "R4") (pin "1") (pinfunction "1_1") (pintype "input"))
      (node (ref "R6") (pin "1") (pinfunction "1_1") (pintype "input"))
      (node (ref "R7") (pin "2") (pinfunction "2_2") (pintype "input"))
      (node (ref "U11") (pin "3") (pinfunction "IN1+_3") (pintype "unspecified"))
      (node (ref "U3") (pin "3") (pinfunction "3_3") (pintype "input"))
    )
    (net (code "33") (name "Net-(U11A-IN1-)") (class "Default")
      (node (ref "C5") (pin "2") (pinfunction "2_2") (pintype "unspecified"))
      (node (ref "R8") (pin "1") (pinfunction "1_1") (pintype "input"))
      (node (ref "R9") (pin "2") (pinfunction "2_2") (pintype "input"))
      (node (ref "U11") (pin "2") (pinfunction "IN1-_2") (pintype "unspecified"))
    )
    (net (code "34") (name "Net-(U11A-OUT1)") (class "Default")
      (node (ref "C5") (pin "1") (pinfunction "1_1") (pintype "unspecified"))
      (node (ref "R11") (pin "3") (pinfunction "3_3") (pintype "input"))
      (node (ref "R9") (pin "1") (pinfunction "1_1") (pintype "input"))
      (node (ref "U11") (pin "1") (pinfunction "OUT1_1") (pintype "output"))
    )
    (net (code "35") (name "Net-(U12A-IN1+)") (class "Default")
      (node (ref "R13") (pin "1") (pinfunction "1_1") (pintype "input"))
      (node (ref "R14") (pin "2") (pinfunction "2_2") (pintype "input"))
      (node (ref "U12") (pin "3") (pinfunction "IN1+_3") (pintype "unspecified"))
    )
    (net (code "36") (name "Net-(U12A-IN1-)") (class "Default")
      (node (ref "C7") (pin "2") (pinfunction "2_2") (pintype "unspecified"))
      (node (ref "R15") (pin "1") (pinfunction "1_1") (pintype "input"))
      (node (ref "R16") (pin "2") (pinfunction "2_2") (pintype "input"))
      (node (ref "U12") (pin "2") (pinfunction "IN1-_2") (pintype "unspecified"))
    )
    (net (code "37") (name "Net-(U13A-IN1+)") (class "Default")
      (node (ref "R25") (pin "1") (pinfunction "1_1") (pintype "unspecified"))
      (node (ref "R26") (pin "2") (pinfunction "2_2") (pintype "unspecified"))
      (node (ref "U13") (pin "3") (pinfunction "IN1+_3") (pintype "unspecified"))
    )
    (net (code "38") (name "OUT2") (class "Default")
      (node (ref "R28") (pin "1") (pinfunction "1_1") (pintype "input"))
      (node (ref "U2") (pin "2") (pinfunction "IN-_2") (pintype "unspecified"))
      (node (ref "U2") (pin "6") (pinfunction "OUT_6") (pintype "output"))
    )
    (net (code "39") (name "OUT3") (class "Default")
      (node (ref "C7") (pin "1") (pinfunction "1_1") (pintype "unspecified"))
      (node (ref "R16") (pin "1") (pinfunction "1_1") (pintype "input"))
      (node (ref "R27") (pin "2") (pinfunction "2_2") (pintype "input"))
      (node (ref "U12") (pin "1") (pinfunction "OUT1_1") (pintype "output"))
    )
    (net (code "40") (name "VCC") (class "Default")
      (node (ref "C15") (pin "2") (pinfunction "2_2") (pintype "unspecified"))
      (node (ref "C19") (pin "2") (pinfunction "2_2") (pintype "unspecified"))
      (node (ref "U10") (pin "4") (pinfunction "EN_4") (pintype "unspecified"))
      (node (ref "U10") (pin "5") (pinfunction "VIN_5") (pintype "unspecified"))
      (node (ref "U9") (pin "4") (pinfunction "EN_4") (pintype "unspecified"))
      (node (ref "U9") (pin "5") (pinfunction "VIN_5") (pintype "unspecified"))
    )
    (net (code "41") (name "VCC3.3") (class "Default")
      (node (ref "C13") (pin "1") (pinfunction "1_1") (pintype "unspecified"))
      (node (ref "C14") (pin "1") (pinfunction "1_1") (pintype "unspecified"))
      (node (ref "C21") (pin "2") (pinfunction "2_2") (pintype "unspecified"))
      (node (ref "C22") (pin "1") (pinfunction "1_1") (pintype "unspecified"))
      (node (ref "D4") (pin "2") (pinfunction "A_2") (pintype "input"))
      (node (ref "L2") (pin "2") (pinfunction "2_2") (pintype "input"))
      (node (ref "R24") (pin "2") (pinfunction "2_2") (pintype "unspecified"))
      (node (ref "R25") (pin "2") (pinfunction "2_2") (pintype "unspecified"))
      (node (ref "U13") (pin "8") (pinfunction "V+_8") (pintype "unspecified"))
      (node (ref "U8") (pin "12") (pinfunction "AVDD_12") (pintype "unspecified"))
      (node (ref "U8") (pin "13") (pinfunction "DVDD_13") (pintype "unspecified"))
      (node (ref "U8") (pin "9") (pinfunction "REFP0_9") (pintype "unspecified"))
    )
    (net (code "42") (name "VCC5") (class "Default")
      (node (ref "C17") (pin "2") (pinfunction "2_2") (pintype "unspecified"))
      (node (ref "C18") (pin "1") (pinfunction "1_1") (pintype "unspecified"))
      (node (ref "C2") (pin "2") (pinfunction "2_2") (pintype "unspecified"))
      (node (ref "C3") (pin "1") (pinfunction "1_1") (pintype "unspecified"))
      (node (ref "C8") (pin "2") (pinfunction "2_2") (pintype "unspecified"))
      (node (ref "D2") (pin "2") (pinfunction "A_2") (pintype "input"))
      (node (ref "H2") (pin "4") (pinfunction "4_4") (pintype "input"))
      (node (ref "L1") (pin "2") (pinfunction "2_2") (pintype "input"))
      (node (ref "R13") (pin "2") (pinfunction "2_2") (pintype "input"))
      (node (ref "R22") (pin "2") (pinfunction "2_2") (pintype "unspecified"))
      (node (ref "R3") (pin "2") (pinfunction "2_2") (pintype "unspecified"))
      (node (ref "R6") (pin "2") (pinfunction "2_2") (pintype "input"))
      (node (ref "U1") (pin "1") (pinfunction "VCC_1") (pintype "unspecified"))
      (node (ref "U11") (pin "8") (pinfunction "V+_8") (pintype "unspecified"))
      (node (ref "U12") (pin "8") (pinfunction "V+_8") (pintype "unspecified"))
      (node (ref "U2") (pin "7") (pinfunction "VCC_7") (pintype "unspecified"))
    )
    (net (code "43") (name "VMID") (class "Default")
      (node (ref "C23") (pin "1") (pinfunction "1_1") (pintype "unspecified"))
      (node (ref "C24") (pin "2") (pinfunction "2_2") (pintype "unspecified"))
      (node (ref "C25") (pin "1") (pinfunction "1_1") (pintype "unspecified"))
      (node (ref "U13") (pin "1") (pinfunction "OUT1_1") (pintype "output"))
      (node (ref "U13") (pin "2") (pinfunction "IN1-_2") (pintype "unspecified"))
      (node (ref "U8") (pin "11") (pinfunction "AIN0/REFP1_11") (pintype "unspecified"))
      (node (ref "U8") (pin "6") (pinfunction "AIN3/REFN1_6") (pintype "unspecified"))
    )
    (net (code "44") (name "unconnected-(U2-NC-Pad1)") (class "Default")
      (node (ref "U2") (pin "1") (pinfunction "NC_1") (pintype "unspecified"))
    )
    (net (code "45") (name "unconnected-(U2-NC-Pad5)") (class "Default")
      (node (ref "U2") (pin "5") (pinfunction "NC_5") (pintype "unspecified"))
    )
  )
)
